# RS485_IO.net
KiCad netlist of a schematic drawn in Altium Designer
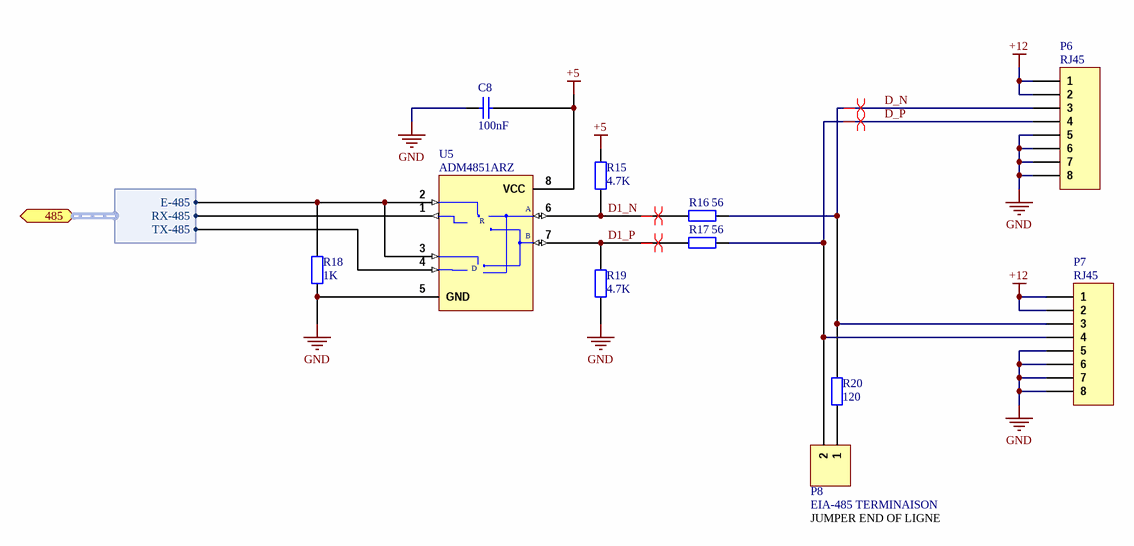
[diagram p0: RS485 IO.SchDoc]

(export (version "E")
  (design (tool "Eeschema 10.0.6"))
  (components
    (comp (ref "C8")
      (value "100nF")
      (footprint "C0805")
      (description "Capacitor")
      (fields
        (field (name "MANUFACTURER") "MULTICOMP")
        (field (name "MANUFACTURER PART NUMBER") "MCCA000296")
      )
      (libsource (lib "BRA") (part "Cap 0805 100nF"))
    )
    (comp (ref "P6")
      (value "RJ45")
      (footprint "SYLANN:Amphenol-RJ45_8")
      (description "Header, 8-Pin")
      (fields (field (name "MANUFACTURER") "MOLEX") (field (name "MANUFACTURER PART NUMBER") "85502-5008"))
      (libsource (lib "Miscellaneous Connectors") (part "Header 8"))
    )
    (comp (ref "P7")
      (value "RJ45")
      (footprint "SYLANN:Amphenol-RJ45_8")
      (description "Header, 8-Pin")
      (fields (field (name "MANUFACTURER") "MOLEX") (field (name "MANUFACTURER PART NUMBER") "85502-5008"))
      (libsource (lib "Miscellaneous Connectors") (part "Header 8"))
    )
    (comp (ref "P8")
      (value "EIA-485 TERMINAISON")
      (footprint "M20_1X2")
      (description "Header, 2-Pin")
      (fields
        (field (name "MANUFACTURER") "HARWIN")
        (field (name "MANUFACTURER PART NUMBER") "M20-8770242")
        (field (name "PUBLISHER") "Altium Limited")
      )
      (libsource (lib "Miscellaneous Connectors") (part "Header 2"))
    )
    (comp (ref "R15")
      (value "4.7K")
      (footprint "R0805")
      (description "Resistor")
      (fields
        (field (name "MANUFACTURER") "MULTICOMP")
        (field (name "MANUFACTURER PART NUMBER") "MC01W080514K7")
      )
      (libsource (lib "BRA") (part "Resistor 0805 4.7K"))
    )
    (comp (ref "R16")
      (value "56")
      (footprint "R0805")
      (description "Resistor")
      (fields
        (field (name "MANUFACTURER") "MULTICOMP")
        (field (name "MANUFACTURER PART NUMBER") "MC01W0805156R")
      )
      (libsource (lib "BRA") (part "Resistor 0805 56"))
    )
    (comp (ref "R17")
      (value "56")
      (footprint "R0805")
      (description "Resistor")
      (fields
        (field (name "MANUFACTURER") "MULTICOMP")
        (field (name "MANUFACTURER PART NUMBER") "MC01W0805156R")
      )
      (libsource (lib "BRA") (part "Resistor 0805 56"))
    )
    (comp (ref "R18")
      (value "1K")
      (footprint "R0805")
      (description "Resistor")
      (fields
        (field (name "MANUFACTURER") "MULTICOMP")
        (field (name "MANUFACTURER PART NUMBER") "MC0.1W08051%1KFR")
      )
      (libsource (lib "BRA") (part "Resistor 0805 1K"))
    )
    (comp (ref "R19")
      (value "4.7K")
      (footprint "R0805")
      (description "Resistor")
      (fields
        (field (name "MANUFACTURER") "MULTICOMP")
        (field (name "MANUFACTURER PART NUMBER") "MC01W080514K7")
      )
      (libsource (lib "BRA") (part "Resistor 0805 4.7K"))
    )
    (comp (ref "R20")
      (value "120")
      (footprint "R0805")
      (description "Resistor")
      (fields
        (field (name "MANUFACTURER") "MULTICOMP")
        (field (name "MANUFACTURER PART NUMBER") "MC01W080516K49")
      )
      (libsource (lib "BRA") (part "Resistor 0805 120"))
    )
    (comp (ref "U5")
      (value "ADM4851ARZ")
      (footprint "SOIC8")
      (description "Low-Power, Slew-Rate-Limited RS-485/RS-422 Transceiver")
      (fields (field (name "MANUFACTURER") "ANALOG DEVICES"))
      (libsource (lib "Maxim Communication Transceiver") (part "MAX485ESA"))
    )
  )
  (nets
    (net (code "2") (name "+5") (class "Default")
      (node (ref "C8") (pin "1") (pinfunction "1_1") (pintype "passive"))
      (node (ref "R15") (pin "2") (pinfunction "2_2") (pintype "passive"))
      (node (ref "U5") (pin "8") (pinfunction "VCC_8") (pintype "power_in"))
    )
    (net (code "3") (name "+12") (class "Default")
      (node (ref "P6") (pin "1") (pinfunction "1_1") (pintype "passive"))
      (node (ref "P6") (pin "2") (pinfunction "2_2") (pintype "passive"))
      (node (ref "P7") (pin "1") (pinfunction "1_1") (pintype "passive"))
      (node (ref "P7") (pin "2") (pinfunction "2_2") (pintype "passive"))
    )
    (net (code "4") (name "/D1_N") (class "Default")
      (node (ref "R15") (pin "1") (pinfunction "1_1") (pintype "passive"))
      (node (ref "R16") (pin "1") (pinfunction "1_1") (pintype "passive"))
      (node (ref "U5") (pin "6") (pinfunction "A_6") (pintype "bidirectional"))
    )
    (net (code "5") (name "/D1_P") (class "Default")
      (node (ref "R17") (pin "1") (pinfunction "1_1") (pintype "passive"))
      (node (ref "R19") (pin "2") (pinfunction "2_2") (pintype "passive"))
      (node (ref "U5") (pin "7") (pinfunction "B_7") (pintype "bidirectional"))
    )
    (net (code "6") (name "/D_N") (class "Default")
      (node (ref "P6") (pin "3") (pinfunction "3_3") (pintype "passive"))
      (node (ref "P7") (pin "3") (pinfunction "3_3") (pintype "passive"))
      (node (ref "R16") (pin "2") (pinfunction "2_2") (pintype "passive"))
      (node (ref "R20") (pin "2") (pinfunction "2_2") (pintype "passive"))
    )
    (net (code "7") (name "/D_P") (class "Default")
      (node (ref "P6") (pin "4") (pinfunction "4_4") (pintype "passive"))
      (node (ref "P7") (pin "4") (pinfunction "4_4") (pintype "passive"))
      (node (ref "P8") (pin "2") (pinfunction "2_2") (pintype "passive"))
      (node (ref "R17") (pin "2") (pinfunction "2_2") (pintype "passive"))
    )
    (net (code "8") (name "/E-485") (class "Default")
      (node (ref "R18") (pin "2") (pinfunction "2_2") (pintype "passive"))
      (node (ref "U5") (pin "2") (pinfunction "~{RE}_2") (pintype "input"))
      (node (ref "U5") (pin "3") (pinfunction "DE_3") (pintype "input"))
    )
    (net (code "9") (name "/RX-485") (class "Default")
      (node (ref "U5") (pin "1") (pinfunction "RO_1") (pintype "output"))
    )
    (net (code "10") (name "/TX-485") (class "Default")
      (node (ref "U5") (pin "4") (pinfunction "DI_4") (pintype "input"))
    )
    (net (code "12") (name "GND") (class "Default")
      (node (ref "C8") (pin "2") (pinfunction "2_2") (pintype "passive"))
      (node (ref "P6") (pin "5") (pinfunction "5_5") (pintype "passive"))
      (node (ref "P6") (pin "6") (pinfunction "6_6") (pintype "passive"))
      (node (ref "P6") (pin "7") (pinfunction "7_7") (pintype "passive"))
      (node (ref "P6") (pin "8") (pinfunction "8_8") (pintype "passive"))
      (node (ref "P7") (pin "5") (pinfunction "5_5") (pintype "passive"))
      (node (ref "P7") (pin "6") (pinfunction "6_6") (pintype "passive"))
      (node (ref "P7") (pin "7") (pinfunction "7_7") (pintype "passive"))
      (node (ref "P7") (pin "8") (pinfunction "8_8") (pintype "passive"))
      (node (ref "R18") (pin "1") (pinfunction "1_1") (pintype "passive"))
      (node (ref "R19") (pin "1") (pinfunction "1_1") (pintype "passive"))
      (node (ref "U5") (pin "5") (pinfunction "GND_5") (pintype "power_in"))
    )
    (net (code "13") (name "Net-(P8-Pad1)") (class "Default")
      (node (ref "P8") (pin "1") (pinfunction "1_1") (pintype "passive"))
      (node (ref "R20") (pin "1") (pinfunction "1_1") (pintype "passive"))
    )
  )
)
